# motor-control-v1.net
KiCad netlist of a schematic drawn in EAGLE
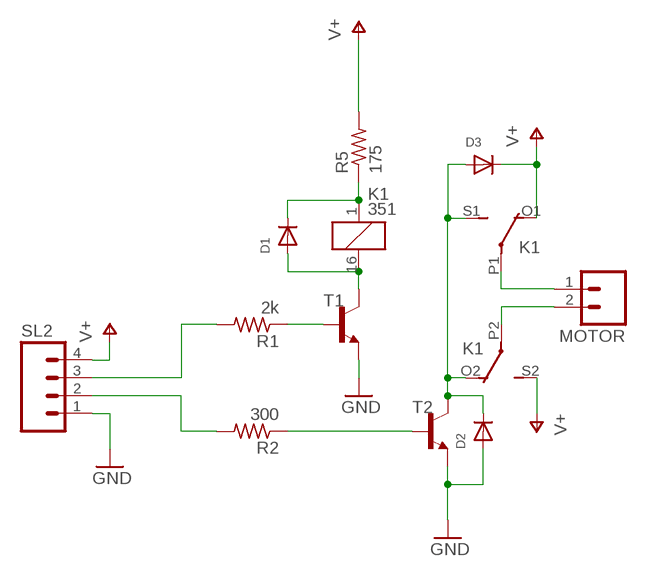
[diagram p0: schematic, sheet 1]

(export (version "E")
  (design (tool "Eeschema 10.0.6"))
  (components
    (comp (ref "D1")
      (value "DIODESMA")
      (footprint "eagle-import:SMADIODE")
      (libsource (lib "eagle-import") (part "DIODESMA"))
    )
    (comp (ref "D2")
      (value "DIODESMA")
      (footprint "eagle-import:SMADIODE")
      (libsource (lib "eagle-import") (part "DIODESMA"))
    )
    (comp (ref "D3")
      (value "DIODESMA")
      (footprint "eagle-import:SMADIODE")
      (libsource (lib "eagle-import") (part "DIODESMA"))
    )
    (comp (ref "K1")
      (value "351")
      (footprint "eagle-import:351")
      (libsource (lib "eagle-import") (part "351"))
    )
    (comp (ref "MOTOR")
      (value "M02")
      (footprint "eagle-import:02P")
      (libsource (lib "eagle-import") (part "M02"))
    )
    (comp (ref "R1")
      (value "2k")
      (footprint "eagle-import:R0603")
      (libsource (lib "eagle-import") (part "R-US_R0603"))
    )
    (comp (ref "R2")
      (value "300")
      (footprint "eagle-import:R0603")
      (libsource (lib "eagle-import") (part "R-US_R0603"))
    )
    (comp (ref "R5")
      (value "175")
      (footprint "eagle-import:R0603")
      (libsource (lib "eagle-import") (part "R-US_R0603"))
    )
    (comp (ref "SL2")
      (value "M04")
      (footprint "eagle-import:04P")
      (libsource (lib "eagle-import") (part "M04"))
    )
    (comp (ref "T1")
      (value "BC808-NPN-SOT23-BEC")
      (footprint "eagle-import:SOT23-BEC")
      (libsource (lib "eagle-import") (part "-NPN-SOT23-BECBC808"))
    )
    (comp (ref "T2")
      (value "BC808-NPN-SOT23-BEC")
      (footprint "eagle-import:SOT23-BEC")
      (libsource (lib "eagle-import") (part "-NPN-SOT23-BECBC808"))
    )
  )
  (nets
    (net (code "1") (name "GND") (class "Default")
      (node (ref "D2") (pin "A") (pinfunction "A_A") (pintype "passive"))
      (node (ref "SL2") (pin "1") (pinfunction "1_1") (pintype "passive"))
      (node (ref "T1") (pin "E") (pinfunction "E_E") (pintype "passive"))
      (node (ref "T2") (pin "E") (pinfunction "E_E") (pintype "passive"))
    )
    (net (code "2") (name "Net-(D1-PadC)") (class "Default")
      (node (ref "D1") (pin "C") (pinfunction "C_C") (pintype "passive"))
      (node (ref "K1") (pin "1") (pinfunction "1_1") (pintype "passive"))
      (node (ref "R5") (pin "1") (pinfunction "1_1") (pintype "passive"))
    )
    (net (code "3") (name "Net-(K1A-2)") (class "Default")
      (node (ref "D1") (pin "A") (pinfunction "A_A") (pintype "passive"))
      (node (ref "K1") (pin "16") (pinfunction "2_16") (pintype "passive"))
      (node (ref "T1") (pin "C") (pinfunction "C_C") (pintype "passive"))
    )
    (net (code "4") (name "Net-(K1B-P)") (class "Default")
      (node (ref "K1") (pin "P1") (pinfunction "P_P1") (pintype "passive"))
      (node (ref "MOTOR") (pin "1") (pinfunction "1_1") (pintype "passive"))
    )
    (net (code "5") (name "Net-(K1B-S)") (class "Default")
      (node (ref "D2") (pin "C") (pinfunction "C_C") (pintype "passive"))
      (node (ref "D3") (pin "A") (pinfunction "A_A") (pintype "passive"))
      (node (ref "K1") (pin "O2") (pinfunction "O_O2") (pintype "passive"))
      (node (ref "K1") (pin "S1") (pinfunction "S_S1") (pintype "passive"))
      (node (ref "T2") (pin "C") (pinfunction "C_C") (pintype "passive"))
    )
    (net (code "6") (name "Net-(K1C-P)") (class "Default")
      (node (ref "K1") (pin "P2") (pinfunction "P_P2") (pintype "passive"))
      (node (ref "MOTOR") (pin "2") (pinfunction "2_2") (pintype "passive"))
    )
    (net (code "7") (name "Net-(R1-Pad1)") (class "Default")
      (node (ref "R1") (pin "1") (pinfunction "1_1") (pintype "passive"))
      (node (ref "T1") (pin "B") (pinfunction "B_B") (pintype "passive"))
    )
    (net (code "8") (name "Net-(R1-Pad2)") (class "Default")
      (node (ref "R1") (pin "2") (pinfunction "2_2") (pintype "passive"))
      (node (ref "SL2") (pin "3") (pinfunction "3_3") (pintype "passive"))
    )
    (net (code "9") (name "Net-(R2-Pad1)") (class "Default")
      (node (ref "R2") (pin "1") (pinfunction "1_1") (pintype "passive"))
      (node (ref "T2") (pin "B") (pinfunction "B_B") (pintype "passive"))
    )
    (net (code "10") (name "Net-(R2-Pad2)") (class "Default")
      (node (ref "R2") (pin "2") (pinfunction "2_2") (pintype "passive"))
      (node (ref "SL2") (pin "2") (pinfunction "2_2") (pintype "passive"))
    )
    (net (code "11") (name "V+") (class "Default")
      (node (ref "D3") (pin "C") (pinfunction "C_C") (pintype "passive"))
      (node (ref "K1") (pin "O1") (pinfunction "O_O1") (pintype "passive"))
      (node (ref "K1") (pin "S2") (pinfunction "S_S2") (pintype "passive"))
      (node (ref "R5") (pin "2") (pinfunction "2_2") (pintype "passive"))
      (node (ref "SL2") (pin "4") (pinfunction "4_4") (pintype "passive"))
    )
  )
)
